# nerves_key5.net
KiCad netlist of a schematic drawn in EAGLE
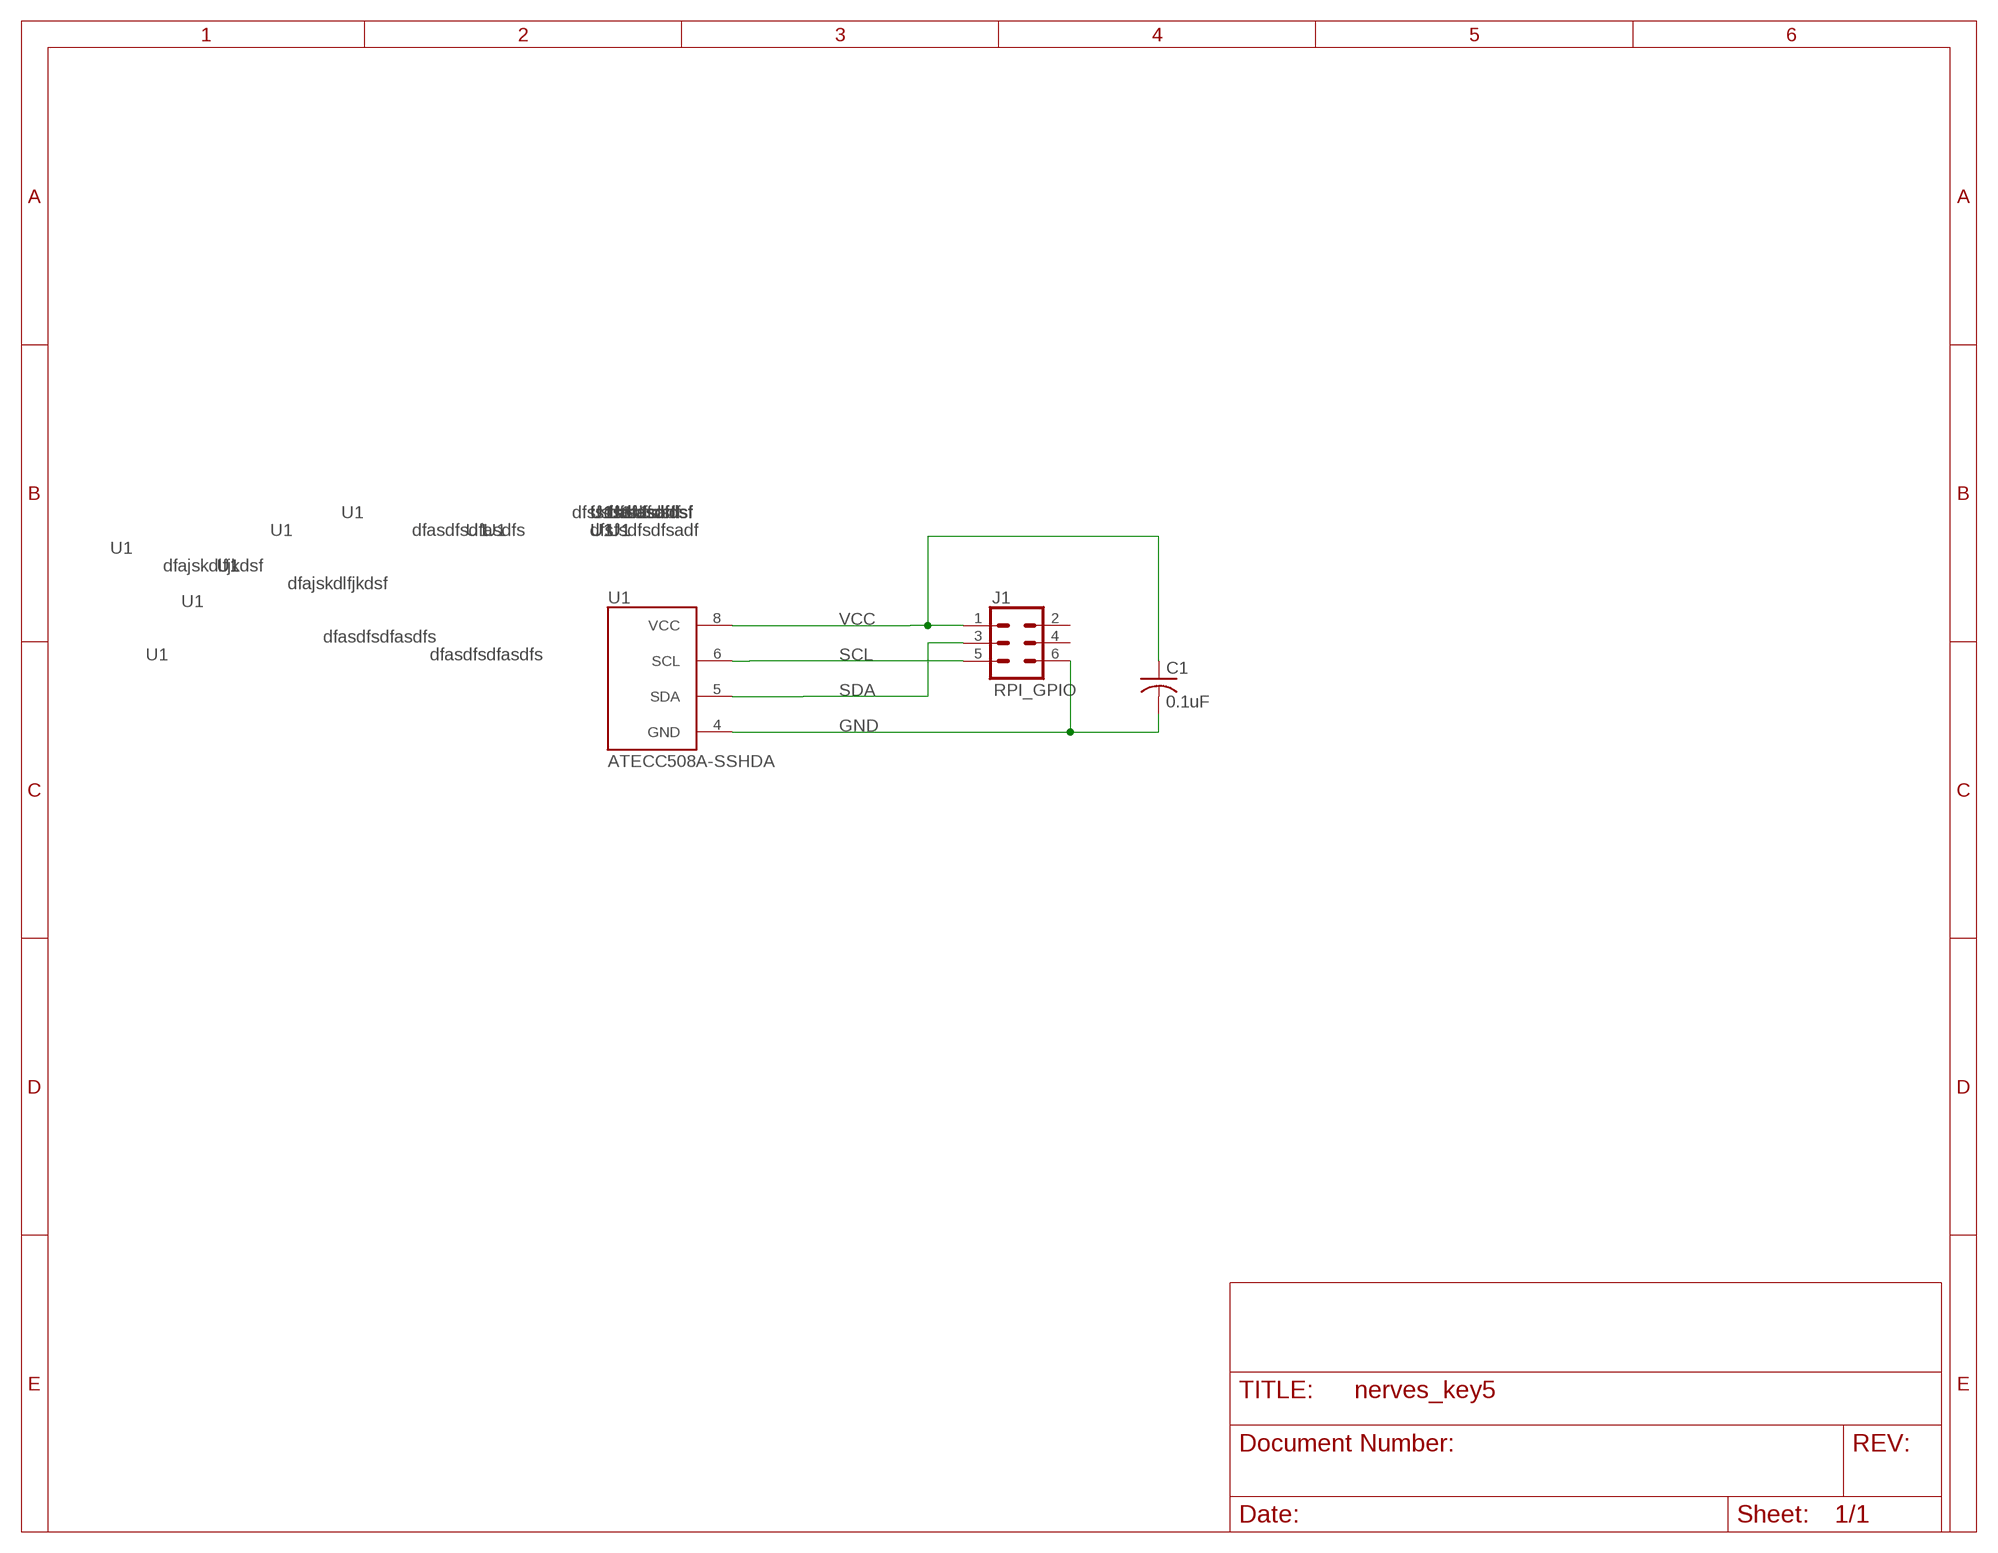
[diagram p0: schematic, sheet 1]

(export (version "E")
  (design (tool "Eeschema 10.0.6"))
  (components
    (comp (ref "C1")
      (value "0.1uF")
      (footprint "eagle-import:C0603")
      (libsource (lib "eagle-import") (part "C-USC0603"))
    )
    (comp (ref "J1")
      (value "RPI_GPIO")
      (footprint "eagle-import:2X3_BIG_HOLES")
      (libsource (lib "eagle-import") (part "CONN_03X2_TIGHT2X3_BIG_HOLES"))
    )
    (comp (ref "U1")
      (value "ATECC508A-SSHDA")
      (footprint "eagle-import:SOIC127P625X175-8")
      (libsource (lib "eagle-import") (part "ATECC508ASOIC-8-NARROW"))
    )
  )
  (nets
    (net (code "1") (name "/GND") (class "Default")
      (node (ref "C1") (pin "2") (pinfunction "2_2") (pintype "passive"))
      (node (ref "J1") (pin "6") (pinfunction "6_6") (pintype "bidirectional"))
      (node (ref "U1") (pin "4") (pinfunction "GND_4") (pintype "bidirectional"))
    )
    (net (code "2") (name "/SCL") (class "Default")
      (node (ref "J1") (pin "5") (pinfunction "5_5") (pintype "bidirectional"))
      (node (ref "U1") (pin "6") (pinfunction "SCL_6") (pintype "bidirectional"))
    )
    (net (code "3") (name "/SDA") (class "Default")
      (node (ref "J1") (pin "3") (pinfunction "3_3") (pintype "bidirectional"))
      (node (ref "U1") (pin "5") (pinfunction "SDA_5") (pintype "bidirectional"))
    )
    (net (code "4") (name "/VCC") (class "Default")
      (node (ref "C1") (pin "1") (pinfunction "1_1") (pintype "passive"))
      (node (ref "J1") (pin "1") (pinfunction "1_1") (pintype "bidirectional"))
      (node (ref "U1") (pin "8") (pinfunction "VCC_8") (pintype "bidirectional"))
    )
    (net (code "5") (name "unconnected-(J1-Pad2)") (class "Default")
      (node (ref "J1") (pin "2") (pinfunction "2_2") (pintype "bidirectional"))
    )
    (net (code "6") (name "unconnected-(J1-Pad4)") (class "Default")
      (node (ref "J1") (pin "4") (pinfunction "4_4") (pintype "bidirectional"))
    )
  )
)
